# Electronic_Sculpture_PCB_rev1.net
KiCad netlist of a schematic drawn in EAGLE
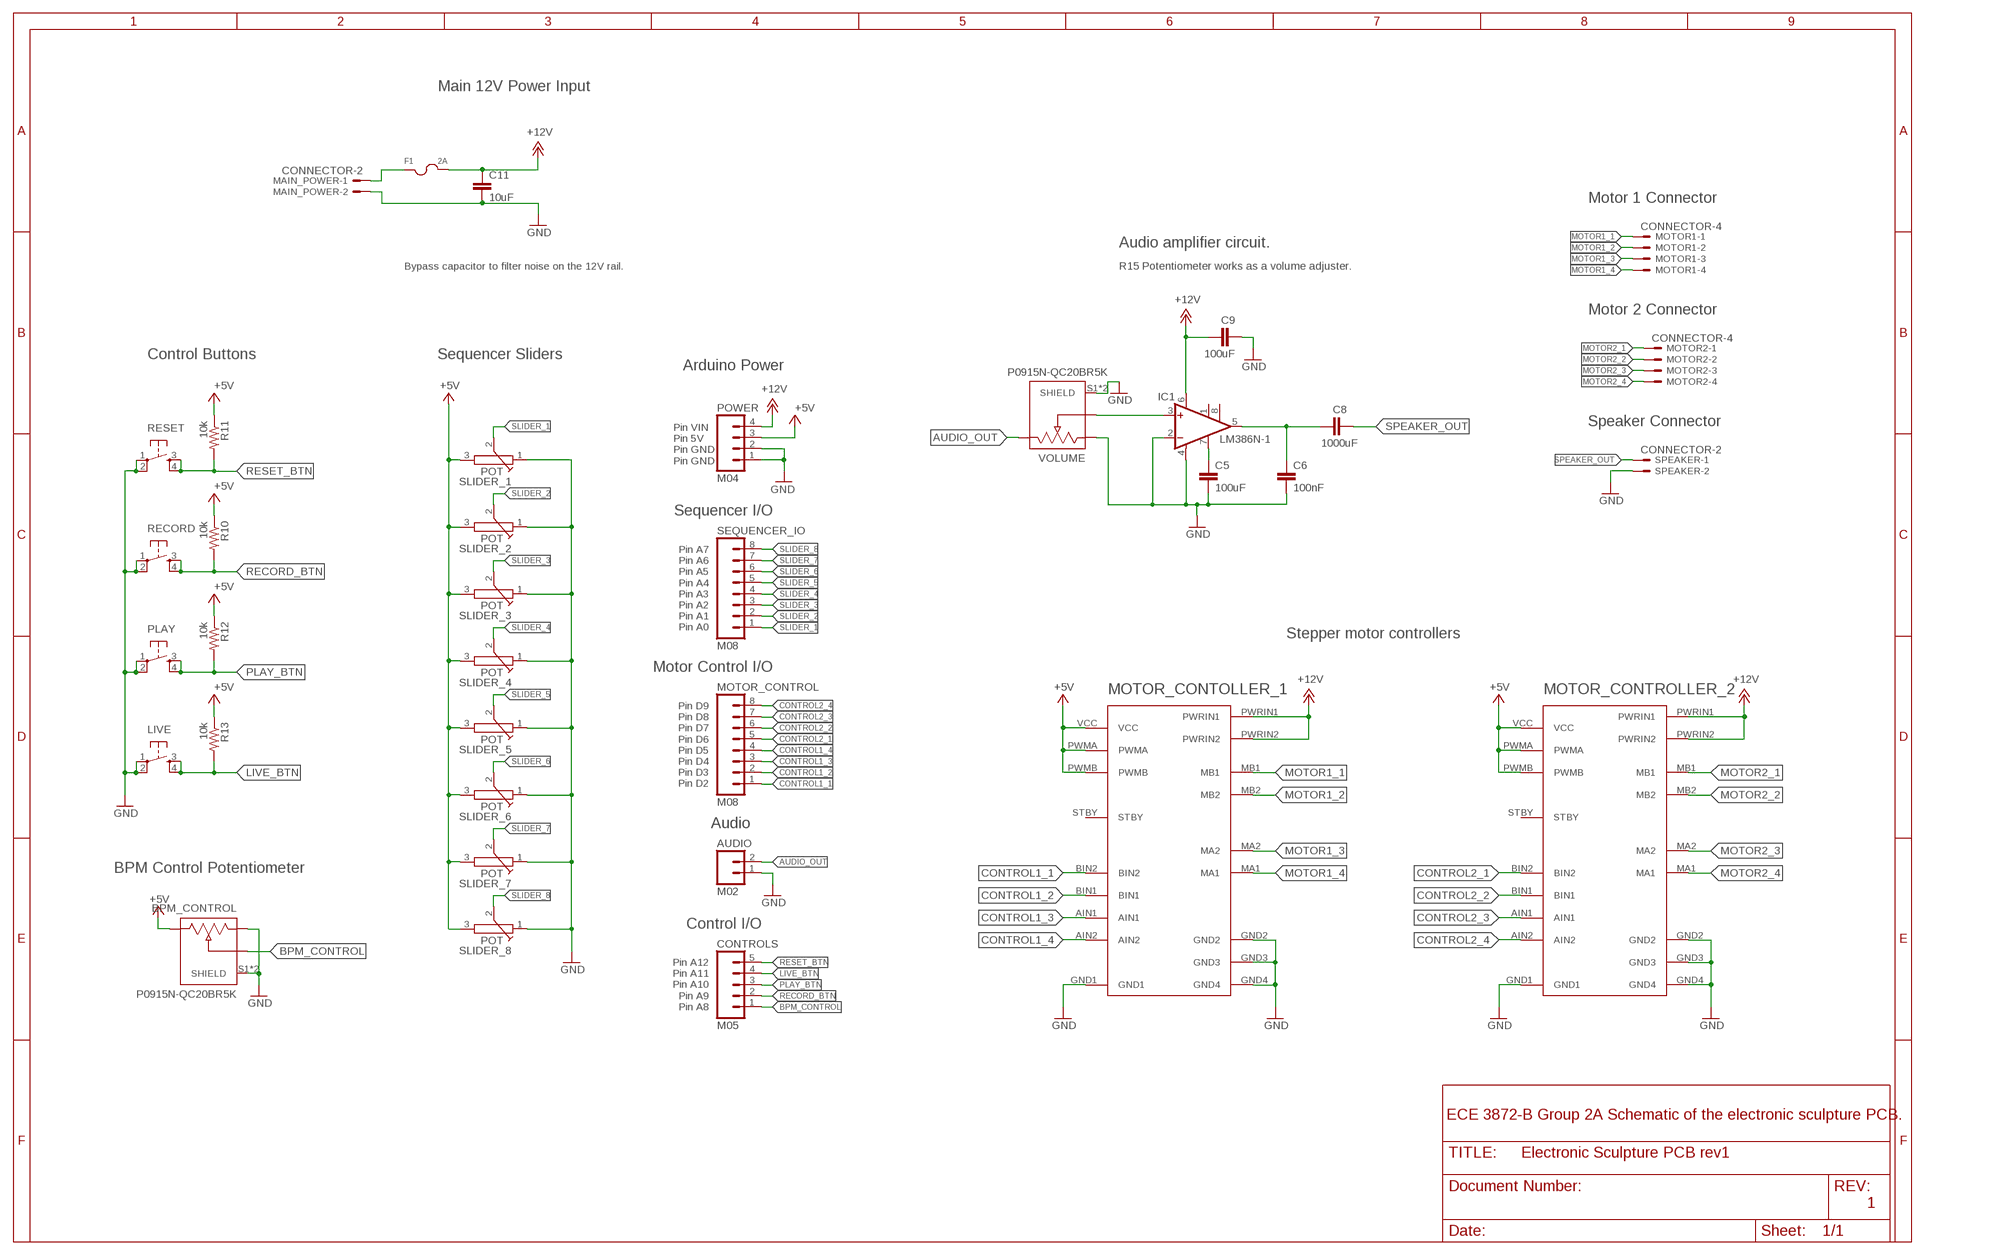
[diagram p0: schematic, sheet 1]

(export (version "E")
  (design (tool "Eeschema 10.0.6"))
  (components
    (comp (ref "AUDIO")
      (value "M02")
      (footprint "eagle-import:1X02")
      (libsource (lib "eagle-import") (part "M02"))
    )
    (comp (ref "BPM_CONTROL")
      (value "P0915N-QC20BR5K")
      (footprint "eagle-import:TRIM_P0915N-QC20BR5K")
      (fields (field (name "MF") "TT Electronics/BI"))
      (libsource (lib "eagle-import") (part "P0915N-QC20BR5K"))
    )
    (comp (ref "C5")
      (value "100uF")
      (footprint "eagle-import:CAP-PTH-5MM")
      (libsource (lib "eagle-import") (part "CAPPTH1"))
    )
    (comp (ref "C6")
      (value "100nF")
      (footprint "eagle-import:CAP-PTH-5MM")
      (libsource (lib "eagle-import") (part "CAPPTH1"))
    )
    (comp (ref "C8")
      (value "1000uF")
      (footprint "eagle-import:CAP-PTH-5MM")
      (libsource (lib "eagle-import") (part "CAPPTH1"))
    )
    (comp (ref "C9")
      (value "100uF")
      (footprint "eagle-import:CAP-PTH-5MM")
      (libsource (lib "eagle-import") (part "CAPPTH1"))
    )
    (comp (ref "C11")
      (value "10uF")
      (footprint "eagle-import:CAP-PTH-5MM")
      (libsource (lib "eagle-import") (part "CAPPTH1"))
    )
    (comp (ref "CONTROLS")
      (value "M05")
      (footprint "eagle-import:1X05")
      (libsource (lib "eagle-import") (part "M05"))
    )
    (comp (ref "F1")
      (value "2A")
      (footprint "eagle-import:MINI-BLADE_FUSE_HOLDER")
      (libsource (lib "eagle-import") (part "FUSE_MINIBLADE"))
    )
    (comp (ref "IC1")
      (value "LM386N-1")
      (footprint "eagle-import:DIL08")
      (libsource (lib "eagle-import") (part "LM386?-N1"))
    )
    (comp (ref "LIVE")
      (value "BIG_PUSHBUTTON")
      (footprint "eagle-import:BIG_PUSHBUTTON")
      (libsource (lib "eagle-import") (part "BIG_PUSHBUTTON"))
    )
    (comp (ref "MAIN_POWER")
      (value "CONNECTOR-2")
      (footprint "eagle-import:MINIFIT_5566-2")
      (libsource (lib "eagle-import") (part "CONNECTOR-2"))
    )
    (comp (ref "MOTOR1")
      (value "CONNECTOR-4")
      (footprint "eagle-import:MINIFIT_5566-4")
      (libsource (lib "eagle-import") (part "CONNECTOR-4"))
    )
    (comp (ref "MOTOR2")
      (value "CONNECTOR-4")
      (footprint "eagle-import:MINIFIT_5566-4")
      (libsource (lib "eagle-import") (part "CONNECTOR-4"))
    )
    (comp (ref "MOTOR_CONTOLLER_1")
      (value "TB6612_BREAKOUT")
      (footprint "eagle-import:TB6612_BREAKOUT")
      (libsource (lib "eagle-import") (part "TB6612_BREAKOUT"))
    )
    (comp (ref "MOTOR_CONTROL")
      (value "M08")
      (footprint "eagle-import:1X08")
      (libsource (lib "eagle-import") (part "M08"))
    )
    (comp (ref "MOTOR_CONTROLLER_2")
      (value "TB6612_BREAKOUT")
      (footprint "eagle-import:TB6612_BREAKOUT")
      (libsource (lib "eagle-import") (part "TB6612_BREAKOUT"))
    )
    (comp (ref "PLAY")
      (value "BIG_PUSHBUTTON")
      (footprint "eagle-import:BIG_PUSHBUTTON")
      (libsource (lib "eagle-import") (part "BIG_PUSHBUTTON"))
    )
    (comp (ref "POWER")
      (value "M04")
      (footprint "eagle-import:1X04")
      (libsource (lib "eagle-import") (part "M04"))
    )
    (comp (ref "R10")
      (value "10k")
      (footprint "eagle-import:AXIAL-0.3")
      (libsource (lib "eagle-import") (part "RESISTORAXIAL-0.3"))
    )
    (comp (ref "R11")
      (value "10k")
      (footprint "eagle-import:AXIAL-0.3")
      (libsource (lib "eagle-import") (part "RESISTORAXIAL-0.3"))
    )
    (comp (ref "R12")
      (value "10k")
      (footprint "eagle-import:AXIAL-0.3")
      (libsource (lib "eagle-import") (part "RESISTORAXIAL-0.3"))
    )
    (comp (ref "R13")
      (value "10k")
      (footprint "eagle-import:AXIAL-0.3")
      (libsource (lib "eagle-import") (part "RESISTORAXIAL-0.3"))
    )
    (comp (ref "RECORD")
      (value "BIG_PUSHBUTTON")
      (footprint "eagle-import:BIG_PUSHBUTTON")
      (libsource (lib "eagle-import") (part "BIG_PUSHBUTTON"))
    )
    (comp (ref "RESET")
      (value "BIG_PUSHBUTTON")
      (footprint "eagle-import:BIG_PUSHBUTTON")
      (libsource (lib "eagle-import") (part "BIG_PUSHBUTTON"))
    )
    (comp (ref "SEQUENCER_IO")
      (value "M08")
      (footprint "eagle-import:1X08")
      (libsource (lib "eagle-import") (part "M08"))
    )
    (comp (ref "SLIDER_1")
      (value "SLIDE_POT")
      (footprint "eagle-import:SLIDE_POT")
      (libsource (lib "eagle-import") (part "SLIDE_POT"))
    )
    (comp (ref "SLIDER_2")
      (value "SLIDE_POT")
      (footprint "eagle-import:SLIDE_POT")
      (libsource (lib "eagle-import") (part "SLIDE_POT"))
    )
    (comp (ref "SLIDER_3")
      (value "SLIDE_POT")
      (footprint "eagle-import:SLIDE_POT")
      (libsource (lib "eagle-import") (part "SLIDE_POT"))
    )
    (comp (ref "SLIDER_4")
      (value "SLIDE_POT")
      (footprint "eagle-import:SLIDE_POT")
      (libsource (lib "eagle-import") (part "SLIDE_POT"))
    )
    (comp (ref "SLIDER_5")
      (value "SLIDE_POT")
      (footprint "eagle-import:SLIDE_POT")
      (libsource (lib "eagle-import") (part "SLIDE_POT"))
    )
    (comp (ref "SLIDER_6")
      (value "SLIDE_POT")
      (footprint "eagle-import:SLIDE_POT")
      (libsource (lib "eagle-import") (part "SLIDE_POT"))
    )
    (comp (ref "SLIDER_7")
      (value "SLIDE_POT")
      (footprint "eagle-import:SLIDE_POT")
      (libsource (lib "eagle-import") (part "SLIDE_POT"))
    )
    (comp (ref "SLIDER_8")
      (value "SLIDE_POT")
      (footprint "eagle-import:SLIDE_POT")
      (libsource (lib "eagle-import") (part "SLIDE_POT"))
    )
    (comp (ref "SPEAKER")
      (value "CONNECTOR-2")
      (footprint "eagle-import:MINIFIT_5566-2")
      (libsource (lib "eagle-import") (part "CONNECTOR-2"))
    )
    (comp (ref "VOLUME")
      (value "P0915N-QC20BR5K")
      (footprint "eagle-import:TRIM_P0915N-QC20BR5K")
      (fields (field (name "MF") "TT Electronics/BI"))
      (libsource (lib "eagle-import") (part "P0915N-QC20BR5K"))
    )
  )
  (nets
    (net (code "1") (name "+5V") (class "Default")
      (node (ref "BPM_CONTROL") (pin "3") (pinfunction "3_3") (pintype "passive"))
      (node (ref "MOTOR_CONTOLLER_1") (pin "PWMA") (pinfunction "PWMA_PWMA") (pintype "bidirectional"))
      (node (ref "MOTOR_CONTOLLER_1") (pin "PWMB") (pinfunction "PWMB_PWMB") (pintype "bidirectional"))
      (node (ref "MOTOR_CONTOLLER_1") (pin "VCC") (pinfunction "VCC_VCC") (pintype "bidirectional"))
      (node (ref "MOTOR_CONTROLLER_2") (pin "PWMA") (pinfunction "PWMA_PWMA") (pintype "bidirectional"))
      (node (ref "MOTOR_CONTROLLER_2") (pin "PWMB") (pinfunction "PWMB_PWMB") (pintype "bidirectional"))
      (node (ref "MOTOR_CONTROLLER_2") (pin "VCC") (pinfunction "VCC_VCC") (pintype "bidirectional"))
      (node (ref "POWER") (pin "3") (pinfunction "3_3") (pintype "passive"))
      (node (ref "R10") (pin "P$1") (pinfunction "1_P$1") (pintype "passive"))
      (node (ref "R11") (pin "P$1") (pinfunction "1_P$1") (pintype "passive"))
      (node (ref "R12") (pin "P$1") (pinfunction "1_P$1") (pintype "passive"))
      (node (ref "R13") (pin "P$1") (pinfunction "1_P$1") (pintype "passive"))
      (node (ref "SLIDER_1") (pin "3") (pinfunction "3_3") (pintype "passive"))
      (node (ref "SLIDER_2") (pin "3") (pinfunction "3_3") (pintype "passive"))
      (node (ref "SLIDER_3") (pin "3") (pinfunction "3_3") (pintype "passive"))
      (node (ref "SLIDER_4") (pin "3") (pinfunction "3_3") (pintype "passive"))
      (node (ref "SLIDER_5") (pin "3") (pinfunction "3_3") (pintype "passive"))
      (node (ref "SLIDER_6") (pin "3") (pinfunction "3_3") (pintype "passive"))
      (node (ref "SLIDER_7") (pin "3") (pinfunction "3_3") (pintype "passive"))
      (node (ref "SLIDER_8") (pin "3") (pinfunction "3_3") (pintype "passive"))
    )
    (net (code "2") (name "+12V") (class "Default")
      (node (ref "C11") (pin "1") (pinfunction "1_1") (pintype "passive"))
      (node (ref "C9") (pin "1") (pinfunction "1_1") (pintype "passive"))
      (node (ref "F1") (pin "R1") (pinfunction "2_R1") (pintype "bidirectional"))
      (node (ref "F1") (pin "R2") (pinfunction "2_R2") (pintype "bidirectional"))
      (node (ref "IC1") (pin "6") (pinfunction "VS_6") (pintype "power_in"))
      (node (ref "MOTOR_CONTOLLER_1") (pin "PWRIN1") (pinfunction "PWRIN1_PWRIN1") (pintype "bidirectional"))
      (node (ref "MOTOR_CONTOLLER_1") (pin "PWRIN2") (pinfunction "PWRIN2_PWRIN2") (pintype "bidirectional"))
      (node (ref "MOTOR_CONTROLLER_2") (pin "PWRIN1") (pinfunction "PWRIN1_PWRIN1") (pintype "bidirectional"))
      (node (ref "MOTOR_CONTROLLER_2") (pin "PWRIN2") (pinfunction "PWRIN2_PWRIN2") (pintype "bidirectional"))
      (node (ref "POWER") (pin "4") (pinfunction "4_4") (pintype "passive"))
    )
    (net (code "3") (name "AUDIO_OUT") (class "Default")
      (node (ref "AUDIO") (pin "2") (pinfunction "2_2") (pintype "passive"))
      (node (ref "VOLUME") (pin "3") (pinfunction "3_3") (pintype "passive"))
    )
    (net (code "4") (name "BPM_CONTROL") (class "Default")
      (node (ref "BPM_CONTROL") (pin "2") (pinfunction "2_2") (pintype "passive"))
      (node (ref "CONTROLS") (pin "1") (pinfunction "1_1") (pintype "passive"))
    )
    (net (code "5") (name "CONTROL1_1") (class "Default")
      (node (ref "MOTOR_CONTOLLER_1") (pin "BIN2") (pinfunction "BIN2_BIN2") (pintype "bidirectional"))
      (node (ref "MOTOR_CONTROL") (pin "1") (pinfunction "1_1") (pintype "passive"))
    )
    (net (code "6") (name "CONTROL1_2") (class "Default")
      (node (ref "MOTOR_CONTOLLER_1") (pin "BIN1") (pinfunction "BIN1_BIN1") (pintype "bidirectional"))
      (node (ref "MOTOR_CONTROL") (pin "2") (pinfunction "2_2") (pintype "passive"))
    )
    (net (code "7") (name "CONTROL1_3") (class "Default")
      (node (ref "MOTOR_CONTOLLER_1") (pin "AIN1") (pinfunction "AIN1_AIN1") (pintype "bidirectional"))
      (node (ref "MOTOR_CONTROL") (pin "3") (pinfunction "3_3") (pintype "passive"))
    )
    (net (code "8") (name "CONTROL1_4") (class "Default")
      (node (ref "MOTOR_CONTOLLER_1") (pin "AIN2") (pinfunction "AIN2_AIN2") (pintype "bidirectional"))
      (node (ref "MOTOR_CONTROL") (pin "4") (pinfunction "4_4") (pintype "passive"))
    )
    (net (code "9") (name "CONTROL2_1") (class "Default")
      (node (ref "MOTOR_CONTROL") (pin "5") (pinfunction "5_5") (pintype "passive"))
      (node (ref "MOTOR_CONTROLLER_2") (pin "BIN2") (pinfunction "BIN2_BIN2") (pintype "bidirectional"))
    )
    (net (code "10") (name "CONTROL2_2") (class "Default")
      (node (ref "MOTOR_CONTROL") (pin "6") (pinfunction "6_6") (pintype "passive"))
      (node (ref "MOTOR_CONTROLLER_2") (pin "BIN1") (pinfunction "BIN1_BIN1") (pintype "bidirectional"))
    )
    (net (code "11") (name "CONTROL2_3") (class "Default")
      (node (ref "MOTOR_CONTROL") (pin "7") (pinfunction "7_7") (pintype "passive"))
      (node (ref "MOTOR_CONTROLLER_2") (pin "AIN1") (pinfunction "AIN1_AIN1") (pintype "bidirectional"))
    )
    (net (code "12") (name "CONTROL2_4") (class "Default")
      (node (ref "MOTOR_CONTROL") (pin "8") (pinfunction "8_8") (pintype "passive"))
      (node (ref "MOTOR_CONTROLLER_2") (pin "AIN2") (pinfunction "AIN2_AIN2") (pintype "bidirectional"))
    )
    (net (code "13") (name "GND") (class "Default")
      (node (ref "AUDIO") (pin "1") (pinfunction "1_1") (pintype "passive"))
      (node (ref "BPM_CONTROL") (pin "1") (pinfunction "1_1") (pintype "passive"))
      (node (ref "BPM_CONTROL") (pin "S1") (pinfunction "SHIELD_S1") (pintype "passive"))
      (node (ref "BPM_CONTROL") (pin "S2") (pinfunction "SHIELD_S2") (pintype "passive"))
      (node (ref "C11") (pin "2") (pinfunction "2_2") (pintype "passive"))
      (node (ref "C5") (pin "2") (pinfunction "2_2") (pintype "passive"))
      (node (ref "C6") (pin "2") (pinfunction "2_2") (pintype "passive"))
      (node (ref "C9") (pin "2") (pinfunction "2_2") (pintype "passive"))
      (node (ref "IC1") (pin "2") (pinfunction "-IN_2") (pintype "input"))
      (node (ref "IC1") (pin "4") (pinfunction "GND_4") (pintype "power_in"))
      (node (ref "LIVE") (pin "1") (pinfunction "P_1") (pintype "passive"))
      (node (ref "LIVE") (pin "2") (pinfunction "P1_2") (pintype "passive"))
      (node (ref "MAIN_POWER") (pin "2") (pinfunction "S_2") (pintype "passive"))
      (node (ref "MOTOR_CONTOLLER_1") (pin "GND1") (pinfunction "GND1_GND1") (pintype "bidirectional"))
      (node (ref "MOTOR_CONTOLLER_1") (pin "GND2") (pinfunction "GND2_GND2") (pintype "bidirectional"))
      (node (ref "MOTOR_CONTOLLER_1") (pin "GND3") (pinfunction "GND3_GND3") (pintype "bidirectional"))
      (node (ref "MOTOR_CONTOLLER_1") (pin "GND4") (pinfunction "GND4_GND4") (pintype "bidirectional"))
      (node (ref "MOTOR_CONTROLLER_2") (pin "GND1") (pinfunction "GND1_GND1") (pintype "bidirectional"))
      (node (ref "MOTOR_CONTROLLER_2") (pin "GND2") (pinfunction "GND2_GND2") (pintype "bidirectional"))
      (node (ref "MOTOR_CONTROLLER_2") (pin "GND3") (pinfunction "GND3_GND3") (pintype "bidirectional"))
      (node (ref "MOTOR_CONTROLLER_2") (pin "GND4") (pinfunction "GND4_GND4") (pintype "bidirectional"))
      (node (ref "PLAY") (pin "1") (pinfunction "P_1") (pintype "passive"))
      (node (ref "PLAY") (pin "2") (pinfunction "P1_2") (pintype "passive"))
      (node (ref "POWER") (pin "1") (pinfunction "1_1") (pintype "passive"))
      (node (ref "POWER") (pin "2") (pinfunction "2_2") (pintype "passive"))
      (node (ref "RECORD") (pin "1") (pinfunction "P_1") (pintype "passive"))
      (node (ref "RECORD") (pin "2") (pinfunction "P1_2") (pintype "passive"))
      (node (ref "RESET") (pin "1") (pinfunction "P_1") (pintype "passive"))
      (node (ref "RESET") (pin "2") (pinfunction "P1_2") (pintype "passive"))
      (node (ref "SLIDER_1") (pin "1") (pinfunction "1_1") (pintype "passive"))
      (node (ref "SLIDER_2") (pin "1") (pinfunction "1_1") (pintype "passive"))
      (node (ref "SLIDER_3") (pin "1") (pinfunction "1_1") (pintype "passive"))
      (node (ref "SLIDER_4") (pin "1") (pinfunction "1_1") (pintype "passive"))
      (node (ref "SLIDER_5") (pin "1") (pinfunction "1_1") (pintype "passive"))
      (node (ref "SLIDER_6") (pin "1") (pinfunction "1_1") (pintype "passive"))
      (node (ref "SLIDER_7") (pin "1") (pinfunction "1_1") (pintype "passive"))
      (node (ref "SLIDER_8") (pin "1") (pinfunction "1_1") (pintype "passive"))
      (node (ref "SPEAKER") (pin "2") (pinfunction "S_2") (pintype "passive"))
      (node (ref "VOLUME") (pin "1") (pinfunction "1_1") (pintype "passive"))
      (node (ref "VOLUME") (pin "S1") (pinfunction "SHIELD_S1") (pintype "passive"))
      (node (ref "VOLUME") (pin "S2") (pinfunction "SHIELD_S2") (pintype "passive"))
    )
    (net (code "14") (name "LIVE_BTN") (class "Default")
      (node (ref "CONTROLS") (pin "4") (pinfunction "4_4") (pintype "passive"))
      (node (ref "LIVE") (pin "3") (pinfunction "S_3") (pintype "passive"))
      (node (ref "LIVE") (pin "4") (pinfunction "S1_4") (pintype "passive"))
      (node (ref "R13") (pin "P$2") (pinfunction "2_P$2") (pintype "passive"))
    )
    (net (code "15") (name "MOTOR1_1") (class "Default")
      (node (ref "MOTOR1") (pin "1") (pinfunction "S_1") (pintype "passive"))
      (node (ref "MOTOR_CONTOLLER_1") (pin "MB1") (pinfunction "MB1_MB1") (pintype "bidirectional"))
    )
    (net (code "16") (name "MOTOR1_2") (class "Default")
      (node (ref "MOTOR1") (pin "2") (pinfunction "S_2") (pintype "passive"))
      (node (ref "MOTOR_CONTOLLER_1") (pin "MB2") (pinfunction "MB2_MB2") (pintype "bidirectional"))
    )
    (net (code "17") (name "MOTOR1_3") (class "Default")
      (node (ref "MOTOR1") (pin "3") (pinfunction "S_3") (pintype "passive"))
      (node (ref "MOTOR_CONTOLLER_1") (pin "MA2") (pinfunction "MA2_MA2") (pintype "bidirectional"))
    )
    (net (code "18") (name "MOTOR1_4") (class "Default")
      (node (ref "MOTOR1") (pin "4") (pinfunction "S_4") (pintype "passive"))
      (node (ref "MOTOR_CONTOLLER_1") (pin "MA1") (pinfunction "MA1_MA1") (pintype "bidirectional"))
    )
    (net (code "19") (name "MOTOR2_1") (class "Default")
      (node (ref "MOTOR2") (pin "1") (pinfunction "S_1") (pintype "passive"))
      (node (ref "MOTOR_CONTROLLER_2") (pin "MB1") (pinfunction "MB1_MB1") (pintype "bidirectional"))
    )
    (net (code "20") (name "MOTOR2_2") (class "Default")
      (node (ref "MOTOR2") (pin "2") (pinfunction "S_2") (pintype "passive"))
      (node (ref "MOTOR_CONTROLLER_2") (pin "MB2") (pinfunction "MB2_MB2") (pintype "bidirectional"))
    )
    (net (code "21") (name "MOTOR2_3") (class "Default")
      (node (ref "MOTOR2") (pin "3") (pinfunction "S_3") (pintype "passive"))
      (node (ref "MOTOR_CONTROLLER_2") (pin "MA2") (pinfunction "MA2_MA2") (pintype "bidirectional"))
    )
    (net (code "22") (name "MOTOR2_4") (class "Default")
      (node (ref "MOTOR2") (pin "4") (pinfunction "S_4") (pintype "passive"))
      (node (ref "MOTOR_CONTROLLER_2") (pin "MA1") (pinfunction "MA1_MA1") (pintype "bidirectional"))
    )
    (net (code "23") (name "Net-(IC1-+IN)") (class "Default")
      (node (ref "IC1") (pin "3") (pinfunction "+IN_3") (pintype "input"))
      (node (ref "VOLUME") (pin "2") (pinfunction "2_2") (pintype "passive"))
    )
    (net (code "24") (name "Net-(IC1-BYPASS)") (class "Default")
      (node (ref "C5") (pin "1") (pinfunction "1_1") (pintype "passive"))
      (node (ref "IC1") (pin "7") (pinfunction "BYPASS_7") (pintype "passive"))
    )
    (net (code "25") (name "Net-(IC1-OUT)") (class "Default")
      (node (ref "C6") (pin "1") (pinfunction "1_1") (pintype "passive"))
      (node (ref "C8") (pin "1") (pinfunction "1_1") (pintype "passive"))
      (node (ref "IC1") (pin "5") (pinfunction "OUT_5") (pintype "output"))
    )
    (net (code "26") (name "Net-(MAIN_POWERA-S)") (class "Default")
      (node (ref "F1") (pin "L1") (pinfunction "1_L1") (pintype "bidirectional"))
      (node (ref "F1") (pin "L2") (pinfunction "1_L2") (pintype "bidirectional"))
      (node (ref "MAIN_POWER") (pin "1") (pinfunction "S_1") (pintype "passive"))
    )
    (net (code "27") (name "PLAY_BTN") (class "Default")
      (node (ref "CONTROLS") (pin "3") (pinfunction "3_3") (pintype "passive"))
      (node (ref "PLAY") (pin "3") (pinfunction "S_3") (pintype "passive"))
      (node (ref "PLAY") (pin "4") (pinfunction "S1_4") (pintype "passive"))
      (node (ref "R12") (pin "P$2") (pinfunction "2_P$2") (pintype "passive"))
    )
    (net (code "28") (name "RECORD_BTN") (class "Default")
      (node (ref "CONTROLS") (pin "2") (pinfunction "2_2") (pintype "passive"))
      (node (ref "R10") (pin "P$2") (pinfunction "2_P$2") (pintype "passive"))
      (node (ref "RECORD") (pin "3") (pinfunction "S_3") (pintype "passive"))
      (node (ref "RECORD") (pin "4") (pinfunction "S1_4") (pintype "passive"))
    )
    (net (code "29") (name "RESET_BTN") (class "Default")
      (node (ref "CONTROLS") (pin "5") (pinfunction "5_5") (pintype "passive"))
      (node (ref "R11") (pin "P$2") (pinfunction "2_P$2") (pintype "passive"))
      (node (ref "RESET") (pin "3") (pinfunction "S_3") (pintype "passive"))
      (node (ref "RESET") (pin "4") (pinfunction "S1_4") (pintype "passive"))
    )
    (net (code "30") (name "SLIDER_1") (class "Default")
      (node (ref "SEQUENCER_IO") (pin "1") (pinfunction "1_1") (pintype "passive"))
      (node (ref "SLIDER_1") (pin "2") (pinfunction "2_2") (pintype "passive"))
    )
    (net (code "31") (name "SLIDER_2") (class "Default")
      (node (ref "SEQUENCER_IO") (pin "2") (pinfunction "2_2") (pintype "passive"))
      (node (ref "SLIDER_2") (pin "2") (pinfunction "2_2") (pintype "passive"))
    )
    (net (code "32") (name "SLIDER_3") (class "Default")
      (node (ref "SEQUENCER_IO") (pin "3") (pinfunction "3_3") (pintype "passive"))
      (node (ref "SLIDER_3") (pin "2") (pinfunction "2_2") (pintype "passive"))
    )
    (net (code "33") (name "SLIDER_4") (class "Default")
      (node (ref "SEQUENCER_IO") (pin "4") (pinfunction "4_4") (pintype "passive"))
      (node (ref "SLIDER_4") (pin "2") (pinfunction "2_2") (pintype "passive"))
    )
    (net (code "34") (name "SLIDER_5") (class "Default")
      (node (ref "SEQUENCER_IO") (pin "5") (pinfunction "5_5") (pintype "passive"))
      (node (ref "SLIDER_5") (pin "2") (pinfunction "2_2") (pintype "passive"))
    )
    (net (code "35") (name "SLIDER_6") (class "Default")
      (node (ref "SEQUENCER_IO") (pin "6") (pinfunction "6_6") (pintype "passive"))
      (node (ref "SLIDER_6") (pin "2") (pinfunction "2_2") (pintype "passive"))
    )
    (net (code "36") (name "SLIDER_7") (class "Default")
      (node (ref "SEQUENCER_IO") (pin "7") (pinfunction "7_7") (pintype "passive"))
      (node (ref "SLIDER_7") (pin "2") (pinfunction "2_2") (pintype "passive"))
    )
    (net (code "37") (name "SLIDER_8") (class "Default")
      (node (ref "SEQUENCER_IO") (pin "8") (pinfunction "8_8") (pintype "passive"))
      (node (ref "SLIDER_8") (pin "2") (pinfunction "2_2") (pintype "passive"))
    )
    (net (code "38") (name "SPEAKER_OUT") (class "Default")
      (node (ref "C8") (pin "2") (pinfunction "2_2") (pintype "passive"))
      (node (ref "SPEAKER") (pin "1") (pinfunction "S_1") (pintype "passive"))
    )
    (net (code "39") (name "unconnected-(IC1-GAIN-Pad1)") (class "Default")
      (node (ref "IC1") (pin "1") (pinfunction "GAIN_1") (pintype "passive"))
    )
    (net (code "40") (name "unconnected-(IC1-GAIN-Pad8)") (class "Default")
      (node (ref "IC1") (pin "8") (pinfunction "GAIN_8") (pintype "passive"))
    )
    (net (code "41") (name "unconnected-(MOTOR_CONTOLLER_1-PadSTBY)") (class "Default")
      (node (ref "MOTOR_CONTOLLER_1") (pin "STBY") (pinfunction "STBY_STBY") (pintype "bidirectional"))
    )
    (net (code "42") (name "unconnected-(MOTOR_CONTROLLER_2-PadSTBY)") (class "Default")
      (node (ref "MOTOR_CONTROLLER_2") (pin "STBY") (pinfunction "STBY_STBY") (pintype "bidirectional"))
    )
  )
)
